# Battery_Charger.net
KiCad netlist of a schematic drawn in Altium Designer
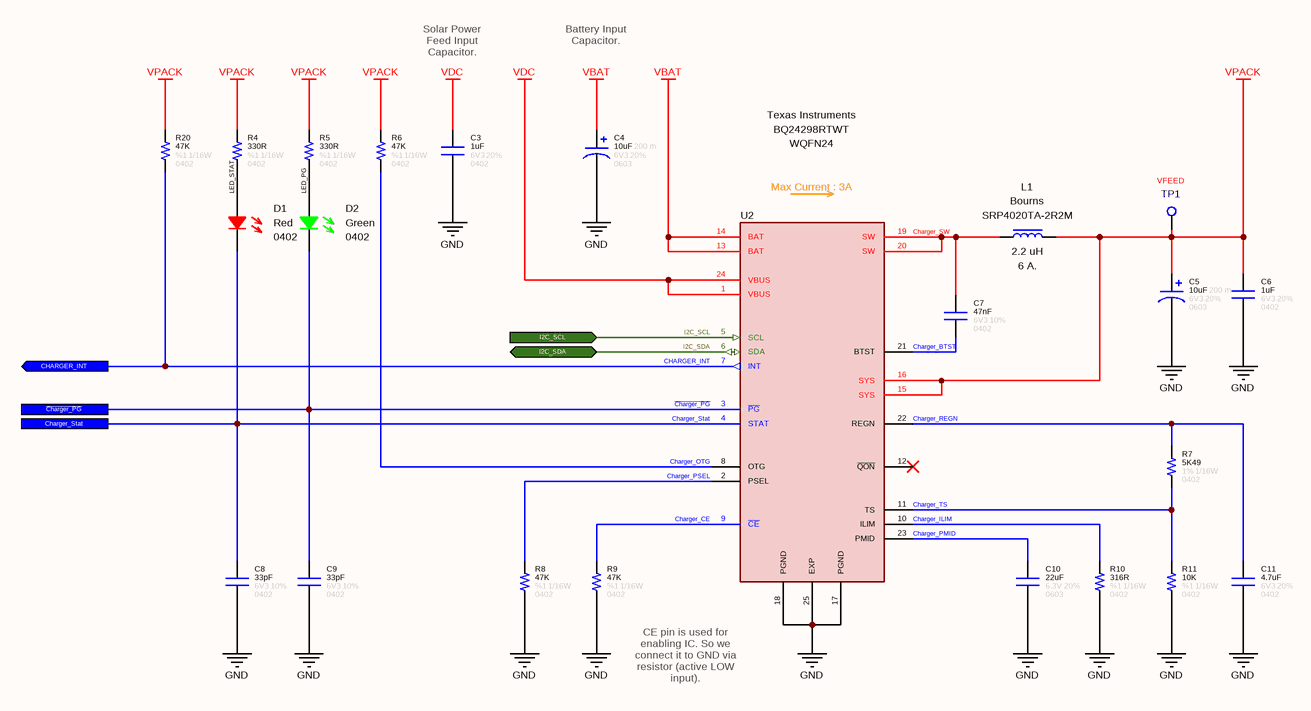
[diagram p0: Battery Charger.SchDoc]

(export (version "E")
  (design (tool "Eeschema 10.0.6"))
  (components
    (comp (ref "C3")
      (value "1uF")
      (footprint "CAPACITOR_0402")
      (description "Multilayer Ceramic Capacitors - SMD - 6.3V 1uF X5R 0402 20%")
      (fields
        (field (name "MANUFACTURER PART NUMBER") "GRM153R60J105ME95D")
        (field (name "TOLERANCE") "20%")
        (field (name "CASE") "0402")
        (field (name "VOLTAGE") "6V3")
        (field (name "Comment") "Capacitor - 1uF [0402] (Ceramic)")
      )
      (libsource (lib "P101DA_Library") (part "Capacitor - 1uF [0402-6V3]"))
    )
    (comp (ref "C4")
      (value "10uF")
      (footprint "CAPACITOR_0603_Tantalum")
      (description "Capacitor - 10uF [0603] (Tantalium)")
      (fields
        (field (name "MANUFACTURER PART NUMBER") "F380J106MMAAH3")
        (field (name "ESR") "200 m")
        (field (name "TOLERANCE") "20%")
        (field (name "CASE") "0603")
        (field (name "VOLTAGE") "6V3")
        (field (name "Comment") "Capacitor - 10uF [0603] (Tantalum)")
      )
      (libsource (lib "P101DA_Library") (part "Capacitor - 10uF [0603-6V3] (Tantalium)"))
    )
    (comp (ref "C5")
      (value "10uF")
      (footprint "CAPACITOR_0603_Tantalum")
      (description "Capacitor - 10uF [0603] (Tantalium)")
      (fields
        (field (name "MANUFACTURER PART NUMBER") "F380J106MMAAH3")
        (field (name "ESR") "200 m")
        (field (name "TOLERANCE") "20%")
        (field (name "CASE") "0603")
        (field (name "VOLTAGE") "6V3")
        (field (name "Comment") "Capacitor - 10uF [0603] (Tantalum)")
      )
      (libsource (lib "P101DA_Library") (part "Capacitor - 10uF [0603-6V3] (Tantalium)"))
    )
    (comp (ref "C6")
      (value "1uF")
      (footprint "CAPACITOR_0402")
      (description "Multilayer Ceramic Capacitors - SMD - 6.3V 1uF X5R 0402 20%")
      (fields
        (field (name "MANUFACTURER PART NUMBER") "GRM153R60J105ME95D")
        (field (name "TOLERANCE") "20%")
        (field (name "CASE") "0402")
        (field (name "VOLTAGE") "6V3")
        (field (name "Comment") "Capacitor - 1uF [0402] (Ceramic)")
      )
      (libsource (lib "P101DA_Library") (part "Capacitor - 1uF [0402-6V3]"))
    )
    (comp (ref "C7")
      (value "47nF")
      (footprint "CAPACITOR_0402")
      (description "Multilayer Ceramic Capacitors - SMD - 6.3V 47nF X7R 0402 10%")
      (fields
        (field (name "MANUFACTURER PART NUMBER") "04026C473KAT2A")
        (field (name "TOLERANCE") "10%")
        (field (name "CASE") "0402")
        (field (name "VOLTAGE") "6V3")
        (field (name "Comment") "Capacitor - 47nF [0402] (Ceramic)")
      )
      (libsource (lib "P101DA_Library") (part "Capacitor - 47nF [0402-6V3]"))
    )
    (comp (ref "C8")
      (value "33pF")
      (footprint "CAPACITOR_0402")
      (description "Capacitor - 33pF [0402] (Ceramic)")
      (fields
        (field (name "MANUFACTURER PART NUMBER") "C0402C330J9RACAUTO")
        (field (name "TOLERANCE") "10%")
        (field (name "CASE") "0402")
        (field (name "VOLTAGE") "6V3")
      )
      (libsource (lib "P101DA_Library") (part "Capacitor - 33pF [0402-6V3]"))
    )
    (comp (ref "C9")
      (value "33pF")
      (footprint "CAPACITOR_0402")
      (description "Capacitor - 33pF [0402] (Ceramic)")
      (fields
        (field (name "MANUFACTURER PART NUMBER") "C0402C330J9RACAUTO")
        (field (name "TOLERANCE") "10%")
        (field (name "CASE") "0402")
        (field (name "VOLTAGE") "6V3")
      )
      (libsource (lib "P101DA_Library") (part "Capacitor - 33pF [0402-6V3]"))
    )
    (comp (ref "C10")
      (value "22uF")
      (footprint "CAPACITOR_0603")
      (description "Multilayer Ceramic Capacitors - SMD - 6V3 22uF X5R 0603 20%")
      (fields
        (field (name "MANUFACTURER PART NUMBER") "GRM188R60J226MEA0D")
        (field (name "TOLERANCE") "20%")
        (field (name "CASE") "0603")
        (field (name "VOLTAGE") "6.3V")
        (field (name "Comment") "Capacitor - 22uF [0603] (Ceramic)")
      )
      (libsource (lib "P101DA_Library") (part "Capacitor - 22uF [0603-6V3]"))
    )
    (comp (ref "C11")
      (value "4.7uF")
      (footprint "CAPACITOR_0402")
      (description "Multilayer Ceramic Capacitors - SMD - 6V3 4.7uF X5R 0402 20%")
      (fields
        (field (name "MANUFACTURER PART NUMBER") "C0402C475M9PACTU")
        (field (name "TOLERANCE") "20%")
        (field (name "CASE") "0402")
        (field (name "VOLTAGE") "6V3")
        (field (name "Comment") "Capacitor - 4.7uF [0402] (Ceramic)")
      )
      (libsource (lib "P101DA_Library") (part "Capacitor - 4.7uF [0402-6V3]"))
    )
    (comp (ref "D1")
      (value "SMD LED (Red)")
      (footprint "LED_0402")
      (description "Standard LEDs - SMD MINI-MOLD ULTRA COMPACT RED")
      (fields
        (field (name "MANUFACTURER PART NUMBER") "SML-P12VTT86R")
        (field (name "CASE") "0402")
        (field (name "COLOR") "Red")
      )
      (libsource (lib "P101DA_Library") (part "Diode - LED (0402-Red)"))
    )
    (comp (ref "D2")
      (value "SMD LED (Green)")
      (footprint "LED_0402")
      (description "Standard LEDs - SMD MINI-MOLD ULTRA COMPACT GREEN")
      (fields
        (field (name "MANUFACTURER PART NUMBER") "SML-P12MTT86R")
        (field (name "CASE") "0402")
        (field (name "COLOR") "Green")
      )
      (libsource (lib "P101DA_Library") (part "Diode - LED (0402-Green)"))
    )
    (comp (ref "L1")
      (value "2.2 uH")
      (footprint "SRP4020TA")
      (description "6 A. 2.2uH Power inducator, 20% tol, SMD, RoHS")
      (fields
        (field (name "TOLERANCE") "20%")
        (field (name "MANUFACTURER NAME") "Bourns")
        (field (name "MANUFACTURER PART NUMBER") "SRP4020TA-2R2M")
        (field (name "MAXIMUM DC CURRENT") "6 A.")
        (field (name "Comment") "SRP4020TA-2R2M")
      )
      (libsource (lib "P101DA_Library") (part "Inductor - SRP4020TA-2R2M"))
    )
    (comp (ref "R4")
      (value "330R")
      (footprint "RESISTOR_0402")
      (description "Thick Film Resistors - SMD 1/16 W 330 Ohm 1%")
      (fields
        (field (name "MANUFACTURER PART NUMBER") "CRCW0402330RFKED")
        (field (name "CASE") "0402")
        (field (name "TOLERANCE") "%1")
        (field (name "POWER") "1/16W")
        (field (name "Comment") "330R - 0402 - %1 - 1/16W")
      )
      (libsource (lib "P101DA_Library") (part "Resistor - 330R [0402]"))
    )
    (comp (ref "R5")
      (value "330R")
      (footprint "RESISTOR_0402")
      (description "Thick Film Resistors - SMD 1/16 W 330 Ohm 1%")
      (fields
        (field (name "MANUFACTURER PART NUMBER") "CRCW0402330RFKED")
        (field (name "CASE") "0402")
        (field (name "TOLERANCE") "%1")
        (field (name "POWER") "1/16W")
        (field (name "Comment") "330R - 0402 - %1 - 1/16W")
      )
      (libsource (lib "P101DA_Library") (part "Resistor - 330R [0402]"))
    )
    (comp (ref "R6")
      (value "47K")
      (footprint "RESISTOR_0402")
      (description "Thick Film Resistors - SMD 1/16 W 47 KOhm 1%")
      (fields
        (field (name "MANUFACTURER PART NUMBER") "CRCW040247K0FKED")
        (field (name "TOLERANCE") "%1")
        (field (name "CASE") "0402")
        (field (name "POWER") "1/16W")
        (field (name "Comment") "47K - 0402 - %1 - 1/16W")
      )
      (libsource (lib "P101DA_Library") (part "Resistor - 47K [0402]"))
    )
    (comp (ref "R7")
      (value "5K49")
      (footprint "RESISTOR_0402")
      (description "Thick Film Resistors - SMD 1/16 W 5.49 KOhm 1%")
      (fields
        (field (name "MANUFACTURER PART NUMBER") "CRCW04025K49FKED")
        (field (name "POWER") "1/16W")
        (field (name "CASE") "0402")
        (field (name "TOLERANCE") "1%")
        (field (name "Comment") "5K49 - 0402 - %1 - 1/16W")
      )
      (libsource (lib "P101DA_Library") (part "Resistor - 5K49 [0402]"))
    )
    (comp (ref "R8")
      (value "47K")
      (footprint "RESISTOR_0402")
      (description "Thick Film Resistors - SMD 1/16 W 47 KOhm 1%")
      (fields
        (field (name "MANUFACTURER PART NUMBER") "CRCW040247K0FKED")
        (field (name "TOLERANCE") "%1")
        (field (name "CASE") "0402")
        (field (name "POWER") "1/16W")
        (field (name "Comment") "47K - 0402 - %1 - 1/16W")
      )
      (libsource (lib "P101DA_Library") (part "Resistor - 47K [0402]"))
    )
    (comp (ref "R9")
      (value "47K")
      (footprint "RESISTOR_0402")
      (description "Thick Film Resistors - SMD 1/16 W 47 KOhm 1%")
      (fields
        (field (name "MANUFACTURER PART NUMBER") "CRCW040247K0FKED")
        (field (name "TOLERANCE") "%1")
        (field (name "CASE") "0402")
        (field (name "POWER") "1/16W")
        (field (name "Comment") "47K - 0402 - %1 - 1/16W")
      )
      (libsource (lib "P101DA_Library") (part "Resistor - 47K [0402]"))
    )
    (comp (ref "R10")
      (value "316R")
      (footprint "RESISTOR_0402")
      (description "Thick Film Resistors - SMD 1/16 W 316 Ohm 1%")
      (fields
        (field (name "MANUFACTURER PART NUMBER") "CRCW0402316RFKED")
        (field (name "POWER") "1/16W")
        (field (name "CASE") "0402")
        (field (name "TOLERANCE") "%1")
        (field (name "Comment") "316R - 0402 - %1 - 1/16W")
      )
      (libsource (lib "P101DA_Library") (part "Resistor - 316R [0402]"))
    )
    (comp (ref "R11")
      (value "10K")
      (footprint "RESISTOR_0402")
      (description "Thick Film Resistors - SMD 1/16 W 10 KOhm 1%")
      (fields
        (field (name "MANUFACTURER PART NUMBER") "CRCW040210K0FKED")
        (field (name "TOLERANCE") "%1")
        (field (name "CASE") "0402")
        (field (name "POWER") "1/16W")
        (field (name "Comment") "10K - 0402 - %1 - 1/16W")
      )
      (libsource (lib "P101DA_Library") (part "Resistor - 10K [0402]"))
    )
    (comp (ref "R20")
      (value "47K")
      (footprint "RESISTOR_0402")
      (description "Thick Film Resistors - SMD 1/16 W 47 KOhm 1%")
      (fields
        (field (name "MANUFACTURER PART NUMBER") "CRCW040247K0FKED")
        (field (name "TOLERANCE") "%1")
        (field (name "CASE") "0402")
        (field (name "POWER") "1/16W")
        (field (name "Comment") "47K - 0402 - %1 - 1/16W")
      )
      (libsource (lib "P101DA_Library") (part "Resistor - 47K [0402]"))
    )
    (comp (ref "TP1")
      (value "~")
      (footprint "Test_Point")
      (description "Test Point")
      (fields (field (name "NAME") "VFEED"))
      (libsource (lib "P101DA_Library") (part "Test Point"))
    )
    (comp (ref "U2")
      (value "BQ24298RTWT")
      (footprint "WQFN-24")
      (description "I2C Controlled 3A Single Cell Charger")
      (fields
        (field (name "MANUFACTURER NAME") "Texas Instruments")
        (field (name "MANUFACTURER PART NUMBER") "BQ24298RTWT")
        (field (name "CASE") "WQFN24")
      )
      (libsource (lib "P101DA_Library") (part "IC - BQ24298RTWT"))
    )
  )
  (nets
    (net (code "1") (name "/CHARGER_INT") (class "Default")
      (node (ref "R20") (pin "1") (pinfunction "1_1") (pintype "passive"))
      (node (ref "U2") (pin "7") (pinfunction "INT_7") (pintype "output"))
    )
    (net (code "2") (name "/Charger_BTST") (class "Default")
      (node (ref "C7") (pin "1") (pinfunction "1_1") (pintype "passive"))
      (node (ref "U2") (pin "21") (pinfunction "BTST_21") (pintype "power_in"))
    )
    (net (code "3") (name "/Charger_CE") (class "Default")
      (node (ref "R9") (pin "2") (pinfunction "2_2") (pintype "passive"))
      (node (ref "U2") (pin "9") (pinfunction "~{CE}_9") (pintype "passive"))
    )
    (net (code "4") (name "/Charger_ILIM") (class "Default")
      (node (ref "R10") (pin "2") (pinfunction "2_2") (pintype "passive"))
      (node (ref "U2") (pin "10") (pinfunction "ILIM_10") (pintype "passive"))
    )
    (net (code "5") (name "/Charger_OTG") (class "Default")
      (node (ref "R6") (pin "1") (pinfunction "1_1") (pintype "passive"))
      (node (ref "U2") (pin "8") (pinfunction "OTG_8") (pintype "passive"))
    )
    (net (code "6") (name "/Charger_PMID") (class "Default")
      (node (ref "C10") (pin "2") (pinfunction "2_2") (pintype "passive"))
      (node (ref "U2") (pin "23") (pinfunction "PMID_23") (pintype "power_in"))
    )
    (net (code "7") (name "/Charger_PSEL") (class "Default")
      (node (ref "R8") (pin "2") (pinfunction "2_2") (pintype "passive"))
      (node (ref "U2") (pin "2") (pinfunction "PSEL_2") (pintype "passive"))
    )
    (net (code "8") (name "/Charger_REGN") (class "Default")
      (node (ref "C11") (pin "2") (pinfunction "2_2") (pintype "passive"))
      (node (ref "R7") (pin "2") (pinfunction "2_2") (pintype "passive"))
      (node (ref "U2") (pin "22") (pinfunction "REGN_22") (pintype "power_in"))
    )
    (net (code "9") (name "/Charger_SW") (class "Default")
      (node (ref "C7") (pin "2") (pinfunction "2_2") (pintype "passive"))
      (node (ref "L1") (pin "1") (pinfunction "1_1") (pintype "passive"))
      (node (ref "U2") (pin "19") (pinfunction "SW_19") (pintype "power_in"))
      (node (ref "U2") (pin "20") (pinfunction "SW_20") (pintype "power_in"))
    )
    (net (code "10") (name "/Charger_Stat") (class "Default")
      (node (ref "C8") (pin "2") (pinfunction "2_2") (pintype "passive"))
      (node (ref "D1") (pin "1") (pinfunction "1_1") (pintype "passive"))
      (node (ref "U2") (pin "4") (pinfunction "STAT_4") (pintype "passive"))
    )
    (net (code "11") (name "/Charger_TS") (class "Default")
      (node (ref "R11") (pin "2") (pinfunction "2_2") (pintype "passive"))
      (node (ref "R7") (pin "1") (pinfunction "1_1") (pintype "passive"))
      (node (ref "U2") (pin "11") (pinfunction "TS_11") (pintype "passive"))
    )
    (net (code "12") (name "/I2C_SCL") (class "Default")
      (node (ref "U2") (pin "5") (pinfunction "SCL_5") (pintype "input"))
    )
    (net (code "13") (name "/I2C_SDA") (class "Default")
      (node (ref "U2") (pin "6") (pinfunction "SDA_6") (pintype "bidirectional"))
    )
    (net (code "14") (name "/LED_PG") (class "Default")
      (node (ref "D2") (pin "2") (pinfunction "2_2") (pintype "passive"))
      (node (ref "R5") (pin "1") (pinfunction "1_1") (pintype "passive"))
    )
    (net (code "15") (name "/LED_STAT") (class "Default")
      (node (ref "D1") (pin "2") (pinfunction "2_2") (pintype "passive"))
      (node (ref "R4") (pin "1") (pinfunction "1_1") (pintype "passive"))
    )
    (net (code "16") (name "/~{Charger_PG}") (class "Default")
      (node (ref "C9") (pin "2") (pinfunction "2_2") (pintype "passive"))
      (node (ref "D2") (pin "1") (pinfunction "1_1") (pintype "passive"))
      (node (ref "U2") (pin "3") (pinfunction "~{PG}_3") (pintype "passive"))
    )
    (net (code "17") (name "GND") (class "Default")
      (node (ref "C10") (pin "1") (pinfunction "1_1") (pintype "passive"))
      (node (ref "C11") (pin "1") (pinfunction "1_1") (pintype "passive"))
      (node (ref "C3") (pin "1") (pinfunction "1_1") (pintype "passive"))
      (node (ref "C4") (pin "2") (pinfunction "2_2") (pintype "passive"))
      (node (ref "C5") (pin "2") (pinfunction "2_2") (pintype "passive"))
      (node (ref "C6") (pin "1") (pinfunction "1_1") (pintype "passive"))
      (node (ref "C8") (pin "1") (pinfunction "1_1") (pintype "passive"))
      (node (ref "C9") (pin "1") (pinfunction "1_1") (pintype "passive"))
      (node (ref "R10") (pin "1") (pinfunction "1_1") (pintype "passive"))
      (node (ref "R11") (pin "1") (pinfunction "1_1") (pintype "passive"))
      (node (ref "R8") (pin "1") (pinfunction "1_1") (pintype "passive"))
      (node (ref "R9") (pin "1") (pinfunction "1_1") (pintype "passive"))
      (node (ref "U2") (pin "17") (pinfunction "PGND_17") (pintype "power_in"))
      (node (ref "U2") (pin "18") (pinfunction "PGND_18") (pintype "power_in"))
      (node (ref "U2") (pin "25") (pinfunction "EXP_25") (pintype "power_in"))
    )
    (net (code "18") (name "VBAT") (class "Default")
      (node (ref "C4") (pin "1") (pinfunction "1_1") (pintype "passive"))
      (node (ref "U2") (pin "13") (pinfunction "BAT_13") (pintype "power_in"))
      (node (ref "U2") (pin "14") (pinfunction "BAT_14") (pintype "power_in"))
    )
    (net (code "19") (name "VDC") (class "Default")
      (node (ref "C3") (pin "2") (pinfunction "2_2") (pintype "passive"))
      (node (ref "U2") (pin "1") (pinfunction "VBUS_1") (pintype "power_in"))
      (node (ref "U2") (pin "24") (pinfunction "VBUS_24") (pintype "power_in"))
    )
    (net (code "20") (name "VPACK") (class "Default")
      (node (ref "C5") (pin "1") (pinfunction "1_1") (pintype "passive"))
      (node (ref "C6") (pin "2") (pinfunction "2_2") (pintype "passive"))
      (node (ref "L1") (pin "2") (pinfunction "2_2") (pintype "passive"))
      (node (ref "R20") (pin "2") (pinfunction "2_2") (pintype "passive"))
      (node (ref "R4") (pin "2") (pinfunction "2_2") (pintype "passive"))
      (node (ref "R5") (pin "2") (pinfunction "2_2") (pintype "passive"))
      (node (ref "R6") (pin "2") (pinfunction "2_2") (pintype "passive"))
      (node (ref "TP1") (pin "1") (pinfunction "1_1") (pintype "passive"))
      (node (ref "U2") (pin "15") (pinfunction "SYS_15") (pintype "power_in"))
      (node (ref "U2") (pin "16") (pinfunction "SYS_16") (pintype "power_in"))
    )
    (net (code "21") (name "unconnected-(U2-~{QON}-Pad12)") (class "Default")
      (node (ref "U2") (pin "12") (pinfunction "~{QON}_12") (pintype "passive+no_connect"))
    )
  )
)
